# 4_DDR_PHY.net
KiCad netlist of a schematic drawn in Altium Designer
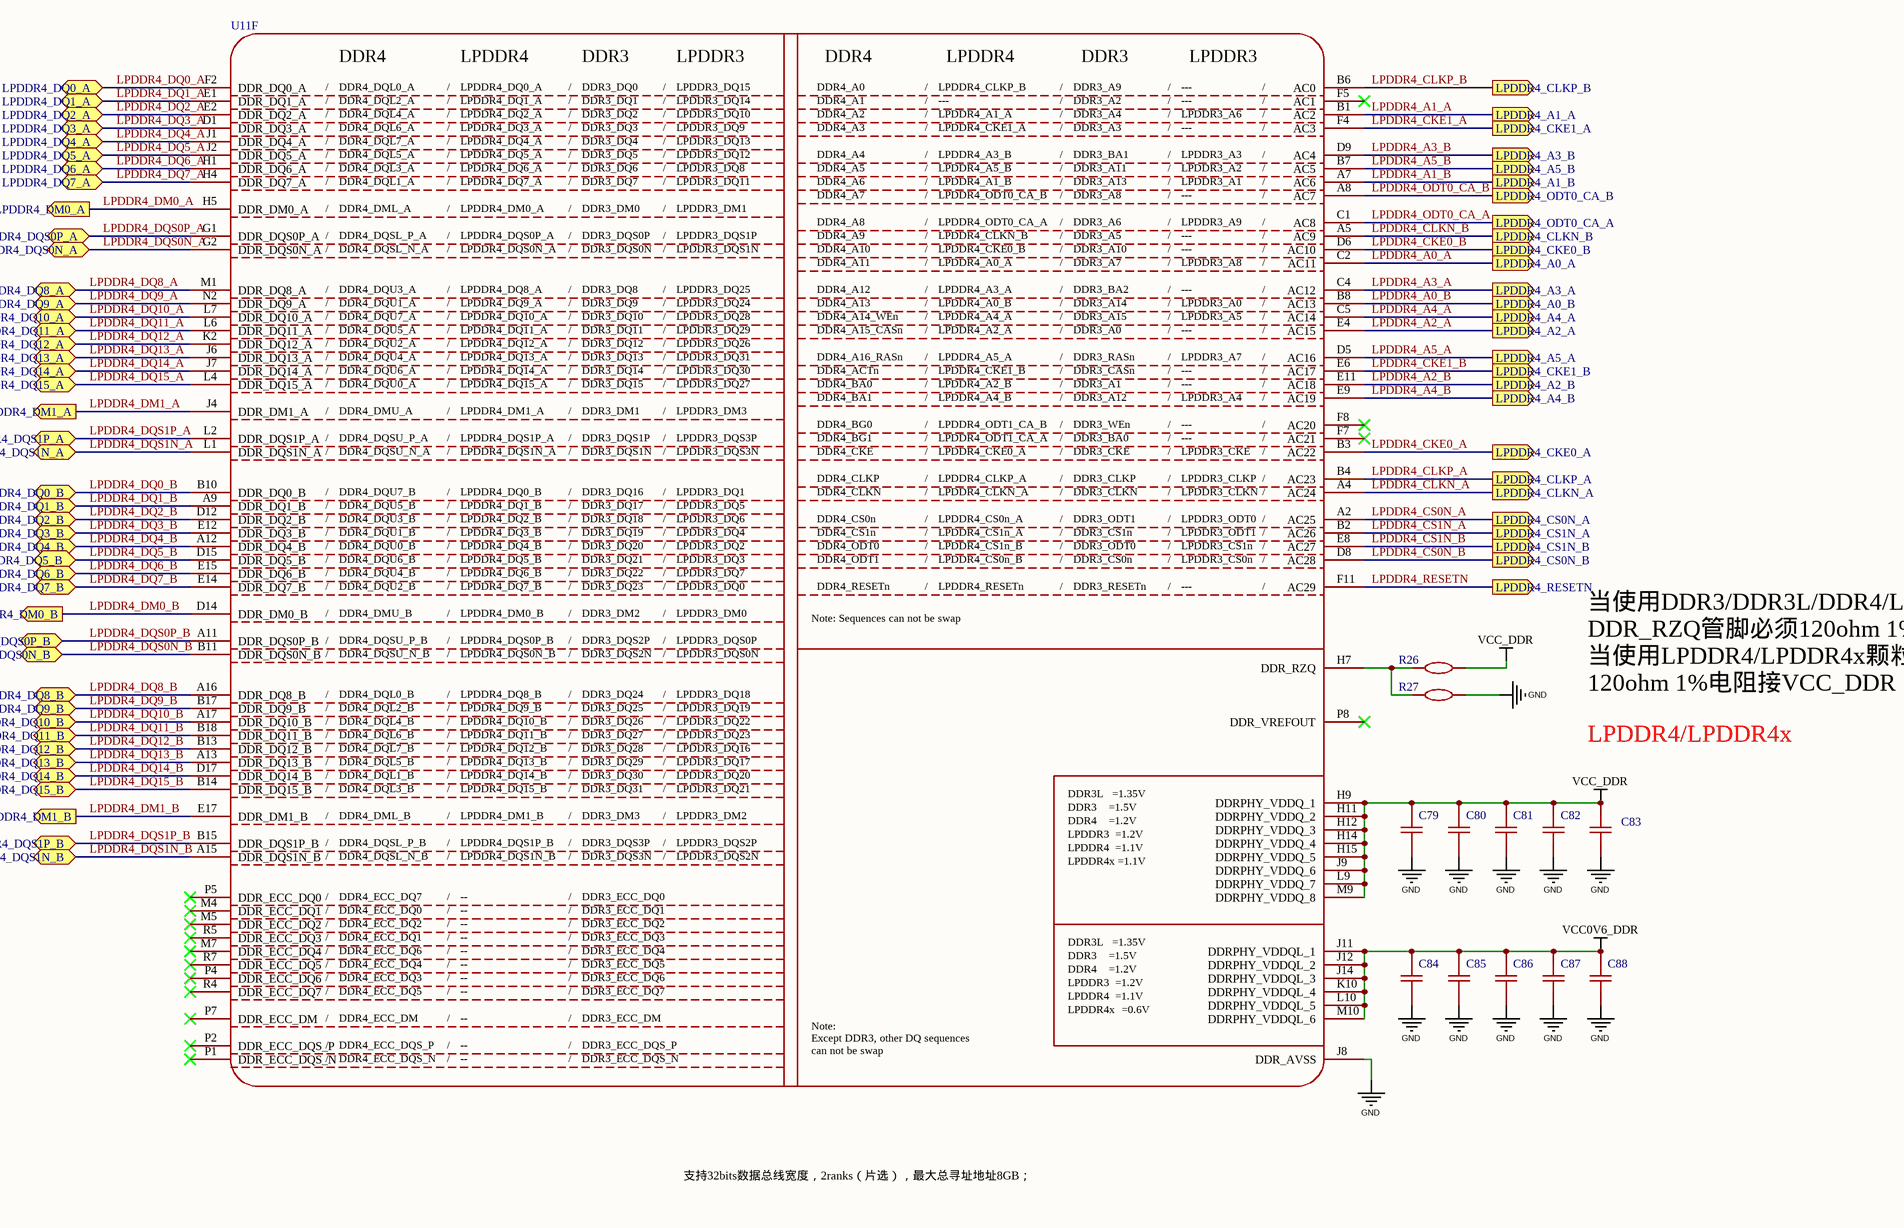
[diagram p0: 4_DDR PHY.schdoc]

(export (version "E")
  (design (tool "Eeschema 10.0.6"))
  (components
    (comp (ref "C79")
      (value "100nF")
      (footprint "C0201")
      (description "容值:100nF;精度:±10%;额定电压:16V;材质(温度系数):X5R;")
      (fields
        (field (name "MANUFACTURER") "SAMSUNG(三星)")
        (field (name "MANUFACTURER PART") "CL03A104KO3NNNC")
      )
      (libsource (lib "altium-import") (part "root_0_CL03A104KO3NNNC_"))
    )
    (comp (ref "C80")
      (value "100nF")
      (footprint "C0201")
      (description "容值:100nF;精度:±10%;额定电压:16V;材质(温度系数):X5R;")
      (fields
        (field (name "MANUFACTURER") "SAMSUNG(三星)")
        (field (name "MANUFACTURER PART") "CL03A104KO3NNNC")
      )
      (libsource (lib "altium-import") (part "root_0_CL03A104KO3NNNC_"))
    )
    (comp (ref "C81")
      (value "4.7uF")
      (footprint "C0201")
      (description "容值:4.7uF;精度:±20%;额定电压:6.3V;材质(温度系数):X5R;")
      (fields
        (field (name "MANUFACTURER") "muRata(村田)")
        (field (name "MANUFACTURER PART") "GRM035R60J475ME15D")
      )
      (libsource (lib "altium-import") (part "root_0_GRM035R60J475ME15D_"))
    )
    (comp (ref "C82")
      (value "4.7uF")
      (footprint "C0201")
      (description "容值:4.7uF;精度:±20%;额定电压:6.3V;材质(温度系数):X5R;")
      (fields
        (field (name "MANUFACTURER") "muRata(村田)")
        (field (name "MANUFACTURER PART") "GRM035R60J475ME15D")
      )
      (libsource (lib "altium-import") (part "root_0_GRM035R60J475ME15D_"))
    )
    (comp (ref "C83")
      (value "10uF")
      (footprint "C0402")
      (description "容值:10uF;精度:±20%;额定电压:10V;材质(温度系数):X5R;")
      (fields
        (field (name "MANUFACTURER") "SAMSUNG(三星)")
        (field (name "MANUFACTURER PART") "CL05A106MP5NUNC")
      )
      (libsource (lib "altium-import") (part "root_1_CL05A106MP5NUNC_"))
    )
    (comp (ref "C84")
      (value "100nF")
      (footprint "C0201")
      (description "容值:100nF;精度:±10%;额定电压:16V;材质(温度系数):X5R;")
      (fields
        (field (name "MANUFACTURER") "SAMSUNG(三星)")
        (field (name "MANUFACTURER PART") "CL03A104KO3NNNC")
      )
      (libsource (lib "altium-import") (part "root_0_CL03A104KO3NNNC_"))
    )
    (comp (ref "C85")
      (value "100nF")
      (footprint "C0201")
      (description "容值:100nF;精度:±10%;额定电压:16V;材质(温度系数):X5R;")
      (fields
        (field (name "MANUFACTURER") "SAMSUNG(三星)")
        (field (name "MANUFACTURER PART") "CL03A104KO3NNNC")
      )
      (libsource (lib "altium-import") (part "root_0_CL03A104KO3NNNC_"))
    )
    (comp (ref "C86")
      (value "4.7uF")
      (footprint "C0201")
      (description "容值:4.7uF;精度:±20%;额定电压:6.3V;材质(温度系数):X5R;")
      (fields
        (field (name "MANUFACTURER") "muRata(村田)")
        (field (name "MANUFACTURER PART") "GRM035R60J475ME15D")
      )
      (libsource (lib "altium-import") (part "root_0_GRM035R60J475ME15D_"))
    )
    (comp (ref "C87")
      (value "4.7uF")
      (footprint "C0201")
      (description "容值:4.7uF;精度:±20%;额定电压:6.3V;材质(温度系数):X5R;")
      (fields
        (field (name "MANUFACTURER") "muRata(村田)")
        (field (name "MANUFACTURER PART") "GRM035R60J475ME15D")
      )
      (libsource (lib "altium-import") (part "root_0_GRM035R60J475ME15D_"))
    )
    (comp (ref "C88")
      (value "4.7uF")
      (footprint "C0201")
      (description "容值:4.7uF;精度:±20%;额定电压:6.3V;材质(温度系数):X5R;")
      (fields
        (field (name "MANUFACTURER") "muRata(村田)")
        (field (name "MANUFACTURER PART") "GRM035R60J475ME15D")
      )
      (libsource (lib "altium-import") (part "root_0_GRM035R60J475ME15D_"))
    )
    (comp (ref "R26")
      (value "120Ω")
      (footprint "R0402")
      (description "电阻类型:厚膜电阻;阻值:120Ω;精度:±1%;功率:62.5mW;最大工作电压:50V;温度系数:±100ppm/℃;")
      (fields
        (field (name "MANUFACTURER") "UNI-ROYAL(厚声)")
        (field (name "MANUFACTURER PART") "0402WGF1200TCE")
      )
      (libsource (lib "altium-import") (part "root_0_0402WGF1200TCE_"))
    )
    (comp (ref "R27")
      (value "NC")
      (footprint "R0402")
      (description "电阻类型:厚膜电阻;阻值:120Ω;精度:±1%;功率:62.5mW;最大工作电压:50V;温度系数:±100ppm/℃;")
      (fields
        (field (name "MANUFACTURER") "UNI-ROYAL(厚声)")
        (field (name "MANUFACTURER PART") "0402WGF1200TCE")
      )
      (libsource (lib "altium-import") (part "root_0_0402WGF1200TCE_"))
    )
    (comp (ref "U11")
      (value "SOC_RK3568")
      (footprint "RK3568")
      (fields (field (name "MANUFACTURER") "Rockchip (瑞芯微)") (field (name "CREATED BY") "JJJ"))
      (libsource (lib "altium-import") (part "root_0_SOC_RK3568_"))
    )
  )
  (nets
    (net (code "1") (name "/LPDDR4_A0_A") (class "Default")
      (node (ref "U11") (pin "C2") (pinfunction "AC11_C2") (pintype "passive"))
    )
    (net (code "2") (name "/LPDDR4_A0_B") (class "Default")
      (node (ref "U11") (pin "B8") (pinfunction "AC13_B8") (pintype "passive"))
    )
    (net (code "3") (name "/LPDDR4_A1_A") (class "Default")
      (node (ref "U11") (pin "B1") (pinfunction "AC2_B1") (pintype "passive"))
    )
    (net (code "4") (name "/LPDDR4_A1_B") (class "Default")
      (node (ref "U11") (pin "A7") (pinfunction "AC6_A7") (pintype "passive"))
    )
    (net (code "5") (name "/LPDDR4_A2_A") (class "Default")
      (node (ref "U11") (pin "E4") (pinfunction "AC15_E4") (pintype "passive"))
    )
    (net (code "6") (name "/LPDDR4_A2_B") (class "Default")
      (node (ref "U11") (pin "E11") (pinfunction "AC18_E11") (pintype "passive"))
    )
    (net (code "7") (name "/LPDDR4_A3_A") (class "Default")
      (node (ref "U11") (pin "C4") (pinfunction "AC12_C4") (pintype "passive"))
    )
    (net (code "8") (name "/LPDDR4_A3_B") (class "Default")
      (node (ref "U11") (pin "D9") (pinfunction "AC4_D9") (pintype "passive"))
    )
    (net (code "9") (name "/LPDDR4_A4_A") (class "Default")
      (node (ref "U11") (pin "C5") (pinfunction "AC14_C5") (pintype "passive"))
    )
    (net (code "10") (name "/LPDDR4_A4_B") (class "Default")
      (node (ref "U11") (pin "E9") (pinfunction "AC19_E9") (pintype "passive"))
    )
    (net (code "11") (name "/LPDDR4_A5_A") (class "Default")
      (node (ref "U11") (pin "D5") (pinfunction "AC16_D5") (pintype "passive"))
    )
    (net (code "12") (name "/LPDDR4_A5_B") (class "Default")
      (node (ref "U11") (pin "B7") (pinfunction "AC5_B7") (pintype "passive"))
    )
    (net (code "13") (name "/LPDDR4_CKE0_A") (class "Default")
      (node (ref "U11") (pin "B3") (pinfunction "AC22_B3") (pintype "passive"))
    )
    (net (code "14") (name "/LPDDR4_CKE0_B") (class "Default")
      (node (ref "U11") (pin "D6") (pinfunction "AC10_D6") (pintype "passive"))
    )
    (net (code "15") (name "/LPDDR4_CKE1_A") (class "Default")
      (node (ref "U11") (pin "F4") (pinfunction "AC3_F4") (pintype "passive"))
    )
    (net (code "16") (name "/LPDDR4_CKE1_B") (class "Default")
      (node (ref "U11") (pin "E6") (pinfunction "AC17_E6") (pintype "passive"))
    )
    (net (code "17") (name "/LPDDR4_CLKN_A") (class "Default")
      (node (ref "U11") (pin "A4") (pinfunction "AC24_A4") (pintype "passive"))
    )
    (net (code "18") (name "/LPDDR4_CLKN_B") (class "Default")
      (node (ref "U11") (pin "A5") (pinfunction "AC9_A5") (pintype "passive"))
    )
    (net (code "19") (name "/LPDDR4_CLKP_A") (class "Default")
      (node (ref "U11") (pin "B4") (pinfunction "AC23_B4") (pintype "passive"))
    )
    (net (code "20") (name "/LPDDR4_CLKP_B") (class "Default")
      (node (ref "U11") (pin "B6") (pinfunction "AC0_B6") (pintype "passive"))
    )
    (net (code "21") (name "/LPDDR4_CS0N_A") (class "Default")
      (node (ref "U11") (pin "A2") (pinfunction "AC25_A2") (pintype "passive"))
    )
    (net (code "22") (name "/LPDDR4_CS0N_B") (class "Default")
      (node (ref "U11") (pin "D8") (pinfunction "AC28_D8") (pintype "passive"))
    )
    (net (code "23") (name "/LPDDR4_CS1N_A") (class "Default")
      (node (ref "U11") (pin "B2") (pinfunction "AC26_B2") (pintype "passive"))
    )
    (net (code "24") (name "/LPDDR4_CS1N_B") (class "Default")
      (node (ref "U11") (pin "E8") (pinfunction "AC27_E8") (pintype "passive"))
    )
    (net (code "25") (name "/LPDDR4_DM0_A") (class "Default")
      (node (ref "U11") (pin "H5") (pinfunction "DDR_DM0_A_H5") (pintype "passive"))
    )
    (net (code "26") (name "/LPDDR4_DM0_B") (class "Default")
      (node (ref "U11") (pin "D14") (pinfunction "DDR_DM0_B_D14") (pintype "passive"))
    )
    (net (code "27") (name "/LPDDR4_DM1_A") (class "Default")
      (node (ref "U11") (pin "J4") (pinfunction "DDR_DM1_A_J4") (pintype "passive"))
    )
    (net (code "28") (name "/LPDDR4_DM1_B") (class "Default")
      (node (ref "U11") (pin "E17") (pinfunction "DDR_DM1_B_E17") (pintype "passive"))
    )
    (net (code "29") (name "/LPDDR4_DQ0_A") (class "Default")
      (node (ref "U11") (pin "F2") (pinfunction "DDR_DQ0_A_F2") (pintype "passive"))
    )
    (net (code "30") (name "/LPDDR4_DQ0_B") (class "Default")
      (node (ref "U11") (pin "B10") (pinfunction "DDR_DQ0_B_B10") (pintype "passive"))
    )
    (net (code "31") (name "/LPDDR4_DQ1_A") (class "Default")
      (node (ref "U11") (pin "E1") (pinfunction "DDR_DQ1_A_E1") (pintype "passive"))
    )
    (net (code "32") (name "/LPDDR4_DQ1_B") (class "Default")
      (node (ref "U11") (pin "A9") (pinfunction "DDR_DQ1_B_A9") (pintype "passive"))
    )
    (net (code "33") (name "/LPDDR4_DQ2_A") (class "Default")
      (node (ref "U11") (pin "E2") (pinfunction "DDR_DQ2_A_E2") (pintype "passive"))
    )
    (net (code "34") (name "/LPDDR4_DQ2_B") (class "Default")
      (node (ref "U11") (pin "D12") (pinfunction "DDR_DQ2_B_D12") (pintype "passive"))
    )
    (net (code "35") (name "/LPDDR4_DQ3_A") (class "Default")
      (node (ref "U11") (pin "D1") (pinfunction "DDR_DQ3_A_D1") (pintype "passive"))
    )
    (net (code "36") (name "/LPDDR4_DQ3_B") (class "Default")
      (node (ref "U11") (pin "E12") (pinfunction "DDR_DQ3_B_E12") (pintype "passive"))
    )
    (net (code "37") (name "/LPDDR4_DQ4_A") (class "Default")
      (node (ref "U11") (pin "J1") (pinfunction "DDR_DQ4_A_J1") (pintype "passive"))
    )
    (net (code "38") (name "/LPDDR4_DQ4_B") (class "Default")
      (node (ref "U11") (pin "A12") (pinfunction "DDR_DQ4_B_A12") (pintype "passive"))
    )
    (net (code "39") (name "/LPDDR4_DQ5_A") (class "Default")
      (node (ref "U11") (pin "J2") (pinfunction "DDR_DQ5_A_J2") (pintype "passive"))
    )
    (net (code "40") (name "/LPDDR4_DQ5_B") (class "Default")
      (node (ref "U11") (pin "D15") (pinfunction "DDR_DQ5_B_D15") (pintype "passive"))
    )
    (net (code "41") (name "/LPDDR4_DQ6_A") (class "Default")
      (node (ref "U11") (pin "H1") (pinfunction "DDR_DQ6_A_H1") (pintype "passive"))
    )
    (net (code "42") (name "/LPDDR4_DQ6_B") (class "Default")
      (node (ref "U11") (pin "E15") (pinfunction "DDR_DQ6_B_E15") (pintype "passive"))
    )
    (net (code "43") (name "/LPDDR4_DQ7_A") (class "Default")
      (node (ref "U11") (pin "H4") (pinfunction "DDR_DQ7_A_H4") (pintype "passive"))
    )
    (net (code "44") (name "/LPDDR4_DQ7_B") (class "Default")
      (node (ref "U11") (pin "E14") (pinfunction "DDR_DQ7_B_E14") (pintype "passive"))
    )
    (net (code "45") (name "/LPDDR4_DQ8_A") (class "Default")
      (node (ref "U11") (pin "M1") (pinfunction "DDR_DQ8_A_M1") (pintype "passive"))
    )
    (net (code "46") (name "/LPDDR4_DQ8_B") (class "Default")
      (node (ref "U11") (pin "A16") (pinfunction "DDR_DQ8_B_A16") (pintype "passive"))
    )
    (net (code "47") (name "/LPDDR4_DQ9_A") (class "Default")
      (node (ref "U11") (pin "N2") (pinfunction "DDR_DQ9_A_N2") (pintype "passive"))
    )
    (net (code "48") (name "/LPDDR4_DQ9_B") (class "Default")
      (node (ref "U11") (pin "B17") (pinfunction "DDR_DQ9_B_B17") (pintype "passive"))
    )
    (net (code "49") (name "/LPDDR4_DQ10_A") (class "Default")
      (node (ref "U11") (pin "L7") (pinfunction "DDR_DQ10_A_L7") (pintype "passive"))
    )
    (net (code "50") (name "/LPDDR4_DQ10_B") (class "Default")
      (node (ref "U11") (pin "A17") (pinfunction "DDR_DQ10_B_A17") (pintype "passive"))
    )
    (net (code "51") (name "/LPDDR4_DQ11_A") (class "Default")
      (node (ref "U11") (pin "L6") (pinfunction "DDR_DQ11_A_L6") (pintype "passive"))
    )
    (net (code "52") (name "/LPDDR4_DQ11_B") (class "Default")
      (node (ref "U11") (pin "B18") (pinfunction "DDR_DQ11_B_B18") (pintype "passive"))
    )
    (net (code "53") (name "/LPDDR4_DQ12_A") (class "Default")
      (node (ref "U11") (pin "K2") (pinfunction "DDR_DQ12_A_K2") (pintype "passive"))
    )
    (net (code "54") (name "/LPDDR4_DQ12_B") (class "Default")
      (node (ref "U11") (pin "B13") (pinfunction "DDR_DQ12_B_B13") (pintype "passive"))
    )
    (net (code "55") (name "/LPDDR4_DQ13_A") (class "Default")
      (node (ref "U11") (pin "J6") (pinfunction "DDR_DQ13_A_J6") (pintype "passive"))
    )
    (net (code "56") (name "/LPDDR4_DQ13_B") (class "Default")
      (node (ref "U11") (pin "A13") (pinfunction "DDR_DQ13_B_A13") (pintype "passive"))
    )
    (net (code "57") (name "/LPDDR4_DQ14_A") (class "Default")
      (node (ref "U11") (pin "J7") (pinfunction "DDR_DQ14_A_J7") (pintype "passive"))
    )
    (net (code "58") (name "/LPDDR4_DQ14_B") (class "Default")
      (node (ref "U11") (pin "D17") (pinfunction "DDR_DQ14_B_D17") (pintype "passive"))
    )
    (net (code "59") (name "/LPDDR4_DQ15_A") (class "Default")
      (node (ref "U11") (pin "L4") (pinfunction "DDR_DQ15_A_L4") (pintype "passive"))
    )
    (net (code "60") (name "/LPDDR4_DQ15_B") (class "Default")
      (node (ref "U11") (pin "B14") (pinfunction "DDR_DQ15_B_B14") (pintype "passive"))
    )
    (net (code "61") (name "/LPDDR4_DQS0N_A") (class "Default")
      (node (ref "U11") (pin "G2") (pinfunction "DDR_DQS0N_A_G2") (pintype "passive"))
    )
    (net (code "62") (name "/LPDDR4_DQS0N_B") (class "Default")
      (node (ref "U11") (pin "B11") (pinfunction "DDR_DQS0N_B_B11") (pintype "passive"))
    )
    (net (code "63") (name "/LPDDR4_DQS0P_A") (class "Default")
      (node (ref "U11") (pin "G1") (pinfunction "DDR_DQS0P_A_G1") (pintype "passive"))
    )
    (net (code "64") (name "/LPDDR4_DQS0P_B") (class "Default")
      (node (ref "U11") (pin "A11") (pinfunction "DDR_DQS0P_B_A11") (pintype "passive"))
    )
    (net (code "65") (name "/LPDDR4_DQS1N_A") (class "Default")
      (node (ref "U11") (pin "L1") (pinfunction "DDR_DQS1N_A_L1") (pintype "passive"))
    )
    (net (code "66") (name "/LPDDR4_DQS1N_B") (class "Default")
      (node (ref "U11") (pin "A15") (pinfunction "DDR_DQS1N_B_A15") (pintype "passive"))
    )
    (net (code "67") (name "/LPDDR4_DQS1P_A") (class "Default")
      (node (ref "U11") (pin "L2") (pinfunction "DDR_DQS1P_A_L2") (pintype "passive"))
    )
    (net (code "68") (name "/LPDDR4_DQS1P_B") (class "Default")
      (node (ref "U11") (pin "B15") (pinfunction "DDR_DQS1P_B_B15") (pintype "passive"))
    )
    (net (code "69") (name "/LPDDR4_ODT0_CA_A") (class "Default")
      (node (ref "U11") (pin "C1") (pinfunction "AC8_C1") (pintype "passive"))
    )
    (net (code "70") (name "/LPDDR4_ODT0_CA_B") (class "Default")
      (node (ref "U11") (pin "A8") (pinfunction "AC7_A8") (pintype "passive"))
    )
    (net (code "71") (name "/LPDDR4_RESETN") (class "Default")
      (node (ref "U11") (pin "F11") (pinfunction "AC29_F11") (pintype "passive"))
    )
    (net (code "72") (name "GND") (class "Default")
      (node (ref "C79") (pin "1") (pinfunction "1_1") (pintype "passive"))
      (node (ref "C80") (pin "1") (pinfunction "1_1") (pintype "passive"))
      (node (ref "C81") (pin "1") (pinfunction "1_1") (pintype "passive"))
      (node (ref "C82") (pin "1") (pinfunction "1_1") (pintype "passive"))
      (node (ref "C83") (pin "1") (pinfunction "1_1") (pintype "passive"))
      (node (ref "C84") (pin "1") (pinfunction "1_1") (pintype "passive"))
      (node (ref "C85") (pin "1") (pinfunction "1_1") (pintype "passive"))
      (node (ref "C86") (pin "1") (pinfunction "1_1") (pintype "passive"))
      (node (ref "C87") (pin "1") (pinfunction "1_1") (pintype "passive"))
      (node (ref "C88") (pin "1") (pinfunction "1_1") (pintype "passive"))
      (node (ref "R27") (pin "2") (pinfunction "2_2") (pintype "passive"))
      (node (ref "U11") (pin "J8") (pinfunction "DDR_AVSS_J8") (pintype "passive"))
    )
    (net (code "73") (name "Net-(U11F-DDR_RZQ)") (class "Default")
      (node (ref "R26") (pin "1") (pinfunction "1_1") (pintype "passive"))
      (node (ref "R27") (pin "1") (pinfunction "1_1") (pintype "passive"))
      (node (ref "U11") (pin "H7") (pinfunction "DDR_RZQ_H7") (pintype "passive"))
    )
    (net (code "74") (name "VCC0V6_DDR") (class "Default")
      (node (ref "C84") (pin "2") (pinfunction "2_2") (pintype "passive"))
      (node (ref "C85") (pin "2") (pinfunction "2_2") (pintype "passive"))
      (node (ref "C86") (pin "2") (pinfunction "2_2") (pintype "passive"))
      (node (ref "C87") (pin "2") (pinfunction "2_2") (pintype "passive"))
      (node (ref "C88") (pin "2") (pinfunction "2_2") (pintype "passive"))
      (node (ref "U11") (pin "J11") (pinfunction "DDRPHY_VDDQL_1_J11") (pintype "passive"))
      (node (ref "U11") (pin "J12") (pinfunction "DDRPHY_VDDQL_2_J12") (pintype "passive"))
      (node (ref "U11") (pin "J14") (pinfunction "DDRPHY_VDDQL_3_J14") (pintype "passive"))
      (node (ref "U11") (pin "K10") (pinfunction "DDRPHY_VDDQL_4_K10") (pintype "passive"))
      (node (ref "U11") (pin "L10") (pinfunction "DDRPHY_VDDQL_5_L10") (pintype "passive"))
      (node (ref "U11") (pin "M10") (pinfunction "DDRPHY_VDDQL_6_M10") (pintype "passive"))
    )
    (net (code "75") (name "VCC_DDR") (class "Default")
      (node (ref "C79") (pin "2") (pinfunction "2_2") (pintype "passive"))
      (node (ref "C80") (pin "2") (pinfunction "2_2") (pintype "passive"))
      (node (ref "C81") (pin "2") (pinfunction "2_2") (pintype "passive"))
      (node (ref "C82") (pin "2") (pinfunction "2_2") (pintype "passive"))
      (node (ref "C83") (pin "2") (pinfunction "2_2") (pintype "passive"))
      (node (ref "R26") (pin "2") (pinfunction "2_2") (pintype "passive"))
      (node (ref "U11") (pin "H11") (pinfunction "DDRPHY_VDDQ_2_H11") (pintype "passive"))
      (node (ref "U11") (pin "H12") (pinfunction "DDRPHY_VDDQ_3_H12") (pintype "passive"))
      (node (ref "U11") (pin "H14") (pinfunction "DDRPHY_VDDQ_4_H14") (pintype "passive"))
      (node (ref "U11") (pin "H15") (pinfunction "DDRPHY_VDDQ_5_H15") (pintype "passive"))
      (node (ref "U11") (pin "H9") (pinfunction "DDRPHY_VDDQ_1_H9") (pintype "passive"))
      (node (ref "U11") (pin "J9") (pinfunction "DDRPHY_VDDQ_6_J9") (pintype "passive"))
      (node (ref "U11") (pin "L9") (pinfunction "DDRPHY_VDDQ_7_L9") (pintype "passive"))
      (node (ref "U11") (pin "M9") (pinfunction "DDRPHY_VDDQ_8_M9") (pintype "passive"))
    )
    (net (code "76") (name "unconnected-(U11F-AC1-PadF5)") (class "Default")
      (node (ref "U11") (pin "F5") (pinfunction "AC1_F5") (pintype "passive+no_connect"))
    )
    (net (code "77") (name "unconnected-(U11F-AC20-PadF8)") (class "Default")
      (node (ref "U11") (pin "F8") (pinfunction "AC20_F8") (pintype "passive+no_connect"))
    )
    (net (code "78") (name "unconnected-(U11F-AC21-PadF7)") (class "Default")
      (node (ref "U11") (pin "F7") (pinfunction "AC21_F7") (pintype "passive+no_connect"))
    )
    (net (code "79") (name "unconnected-(U11F-DDR_ECC_DM-PadP7)") (class "Default")
      (node (ref "U11") (pin "P7") (pinfunction "DDR_ECC_DM_P7") (pintype "passive+no_connect"))
    )
    (net (code "80") (name "unconnected-(U11F-DDR_ECC_DQ0-PadP5)") (class "Default")
      (node (ref "U11") (pin "P5") (pinfunction "DDR_ECC_DQ0_P5") (pintype "passive+no_connect"))
    )
    (net (code "81") (name "unconnected-(U11F-DDR_ECC_DQ1-PadM4)") (class "Default")
      (node (ref "U11") (pin "M4") (pinfunction "DDR_ECC_DQ1_M4") (pintype "passive+no_connect"))
    )
    (net (code "82") (name "unconnected-(U11F-DDR_ECC_DQ2-PadM5)") (class "Default")
      (node (ref "U11") (pin "M5") (pinfunction "DDR_ECC_DQ2_M5") (pintype "passive+no_connect"))
    )
    (net (code "83") (name "unconnected-(U11F-DDR_ECC_DQ3-PadR5)") (class "Default")
      (node (ref "U11") (pin "R5") (pinfunction "DDR_ECC_DQ3_R5") (pintype "passive+no_connect"))
    )
    (net (code "84") (name "unconnected-(U11F-DDR_ECC_DQ4-PadM7)") (class "Default")
      (node (ref "U11") (pin "M7") (pinfunction "DDR_ECC_DQ4_M7") (pintype "passive+no_connect"))
    )
    (net (code "85") (name "unconnected-(U11F-DDR_ECC_DQ5-PadR7)") (class "Default")
      (node (ref "U11") (pin "R7") (pinfunction "DDR_ECC_DQ5_R7") (pintype "passive+no_connect"))
    )
    (net (code "86") (name "unconnected-(U11F-DDR_ECC_DQ6-PadP4)") (class "Default")
      (node (ref "U11") (pin "P4") (pinfunction "DDR_ECC_DQ6_P4") (pintype "passive+no_connect"))
    )
    (net (code "87") (name "unconnected-(U11F-DDR_ECC_DQ7-PadR4)") (class "Default")
      (node (ref "U11") (pin "R4") (pinfunction "DDR_ECC_DQ7_R4") (pintype "passive+no_connect"))
    )
    (net (code "88") (name "unconnected-(U11F-DDR_ECC_DQS_N-PadP1)") (class "Default")
      (node (ref "U11") (pin "P1") (pinfunction "DDR_ECC_DQS_N_P1") (pintype "passive+no_connect"))
    )
    (net (code "89") (name "unconnected-(U11F-DDR_ECC_DQS_P-PadP2)") (class "Default")
      (node (ref "U11") (pin "P2") (pinfunction "DDR_ECC_DQS_P_P2") (pintype "passive+no_connect"))
    )
    (net (code "90") (name "unconnected-(U11F-DDR_VREFOUT-PadP8)") (class "Default")
      (node (ref "U11") (pin "P8") (pinfunction "DDR_VREFOUT_P8") (pintype "passive+no_connect"))
    )
  )
)
